# audio_interface_board.net
KiCad netlist of a schematic drawn in EasyEDA Pro
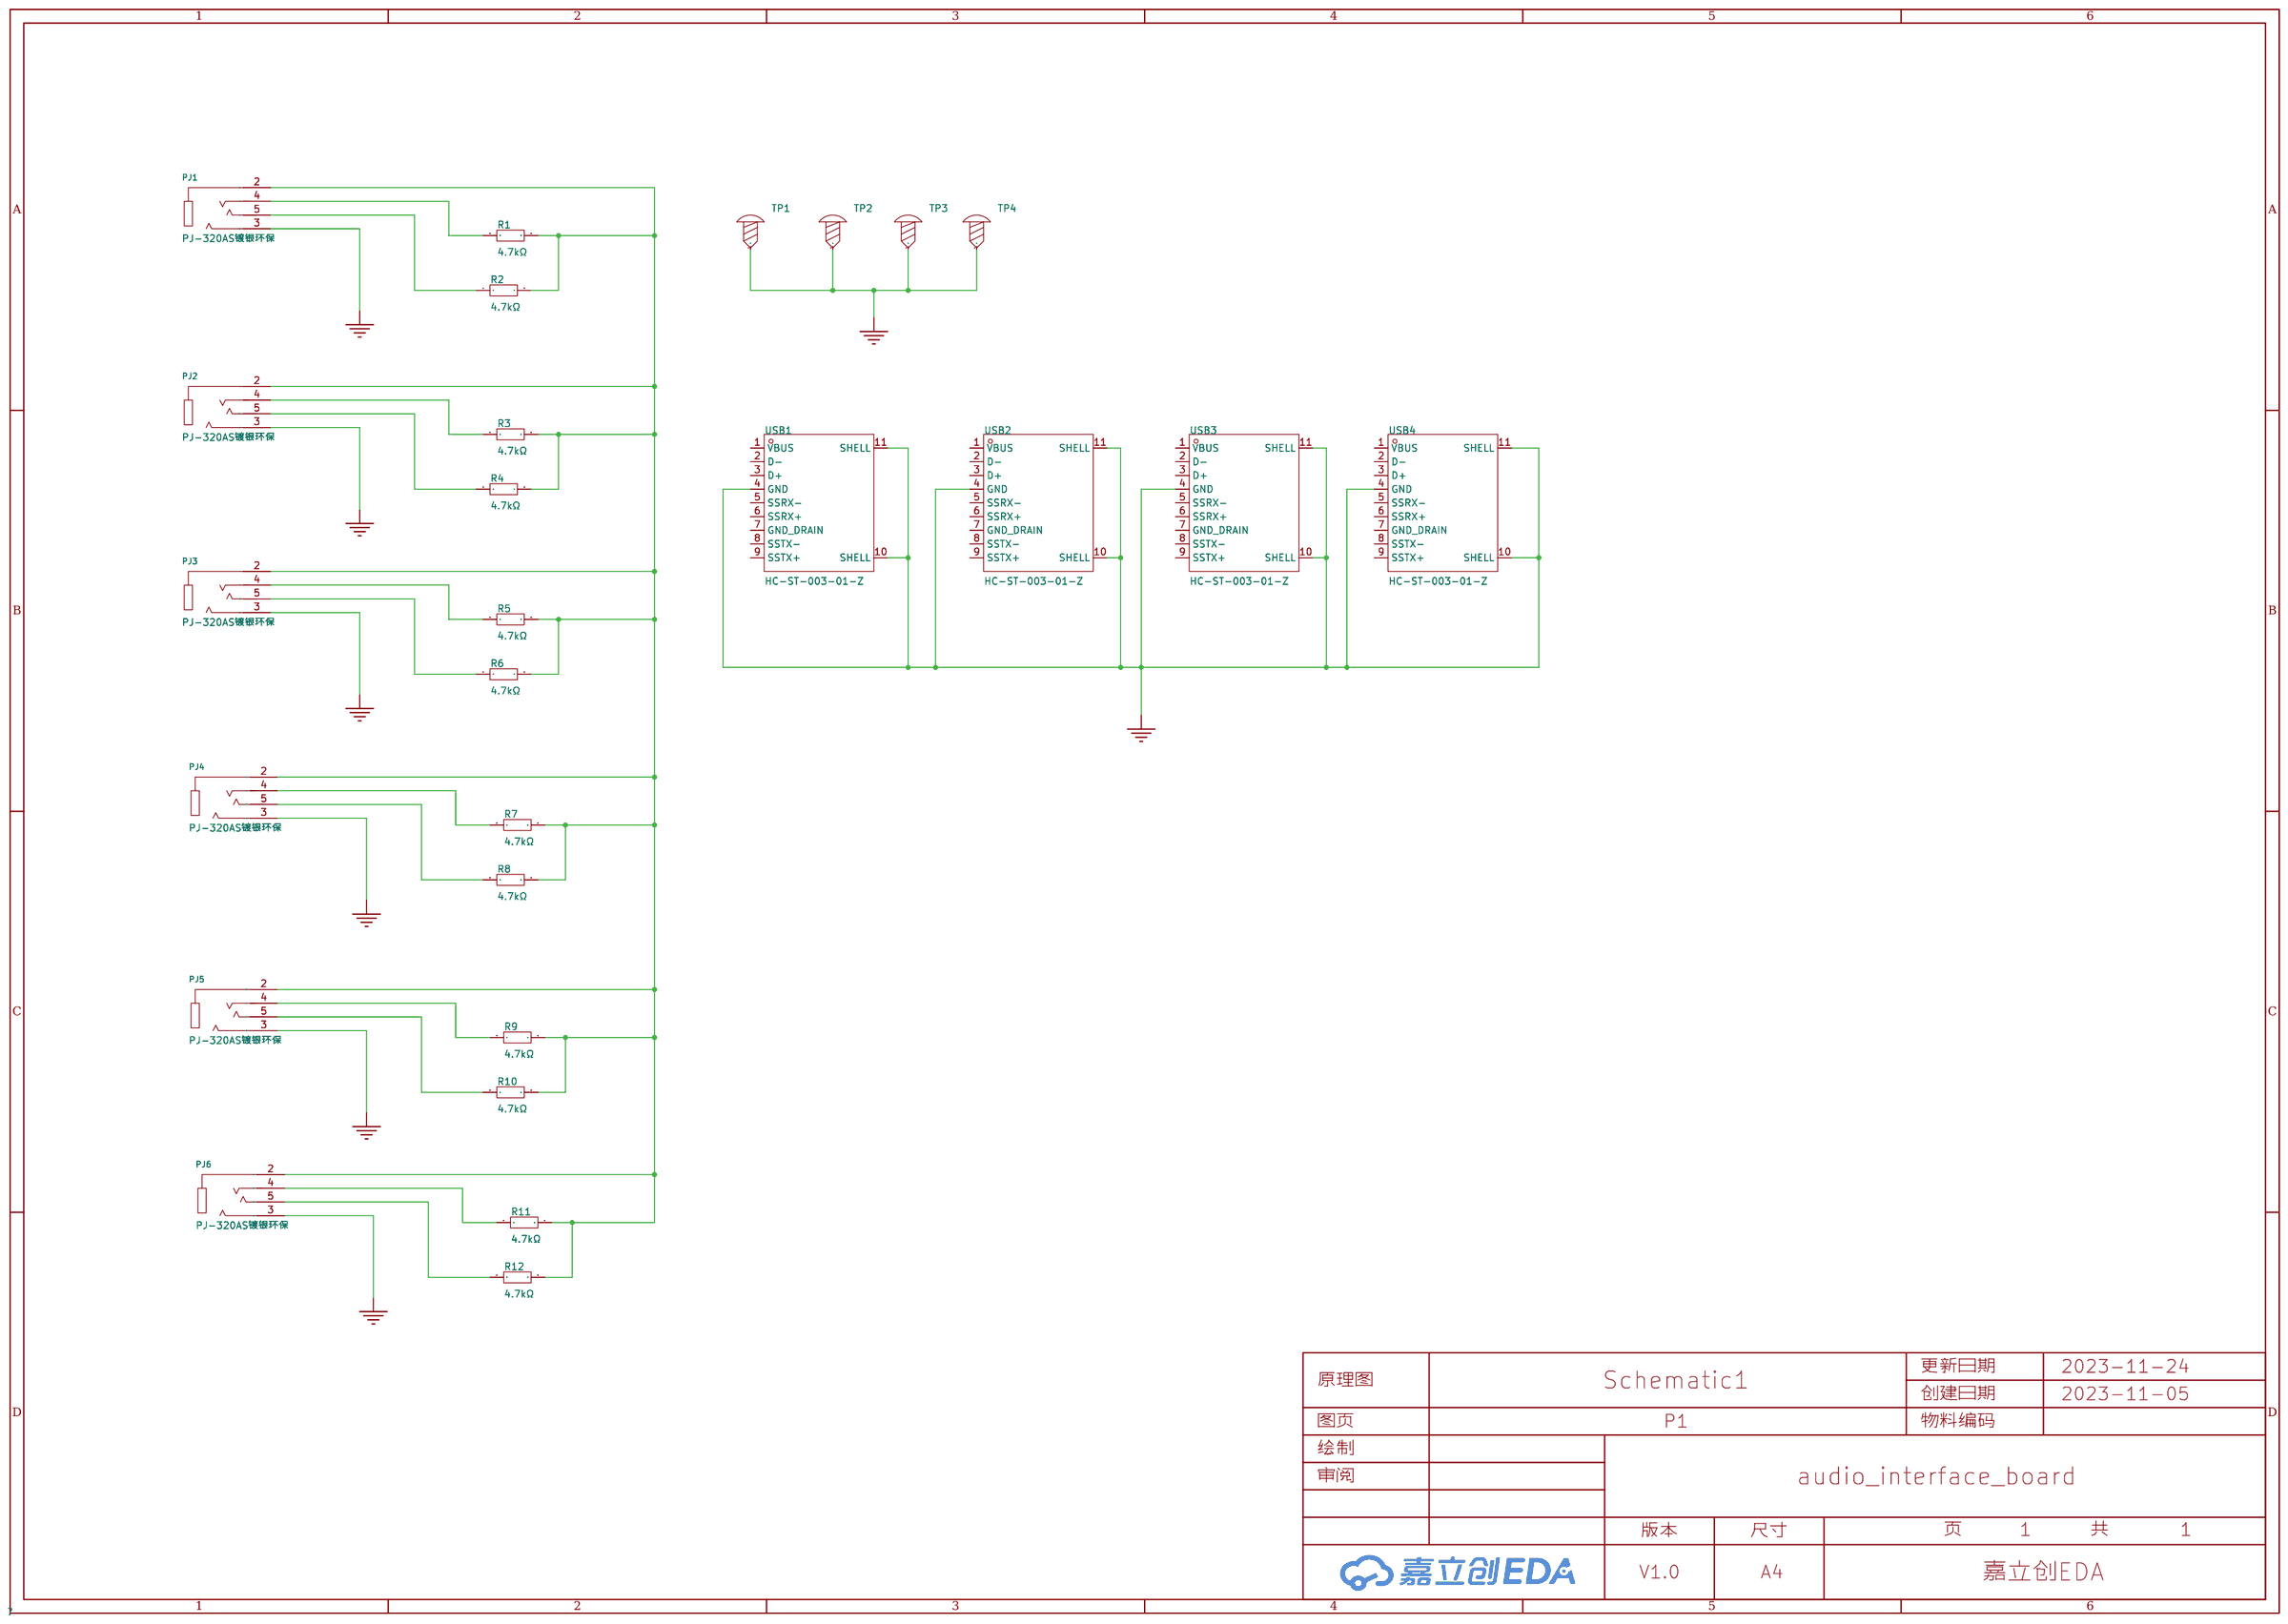
[diagram p0: schematic sheet]

(export (version "E")
  (design (tool "Eeschema 10.0.6"))
  (components
    (comp (ref "PJ1")
      (value "PJ-320AS镀银环保")
      (footprint "easyedapro:AUDIO-TH_HAOYU_PJ-320AS")
      (description "3.5mm耳机插座")
      (fields (field (name "Manufacturer") "HOOYA(皓宇电子)"))
      (libsource (lib "easyedapro") (part "PJ-320AS"))
    )
    (comp (ref "PJ2")
      (value "PJ-320AS镀银环保")
      (footprint "easyedapro:AUDIO-TH_HAOYU_PJ-320AS")
      (description "3.5mm耳机插座")
      (fields (field (name "Manufacturer") "HOOYA(皓宇电子)"))
      (libsource (lib "easyedapro") (part "PJ-320AS"))
    )
    (comp (ref "PJ3")
      (value "PJ-320AS镀银环保")
      (footprint "easyedapro:AUDIO-TH_HAOYU_PJ-320AS")
      (description "3.5mm耳机插座")
      (fields (field (name "Manufacturer") "HOOYA(皓宇电子)"))
      (libsource (lib "easyedapro") (part "PJ-320AS"))
    )
    (comp (ref "PJ4")
      (value "PJ-320AS镀银环保")
      (footprint "easyedapro:AUDIO-TH_HAOYU_PJ-320AS")
      (description "3.5mm耳机插座")
      (fields (field (name "Manufacturer") "HOOYA(皓宇电子)"))
      (libsource (lib "easyedapro") (part "PJ-320AS"))
    )
    (comp (ref "PJ5")
      (value "PJ-320AS镀银环保")
      (footprint "easyedapro:AUDIO-TH_HAOYU_PJ-320AS")
      (description "3.5mm耳机插座")
      (fields (field (name "Manufacturer") "HOOYA(皓宇电子)"))
      (libsource (lib "easyedapro") (part "PJ-320AS"))
    )
    (comp (ref "PJ6")
      (value "PJ-320AS镀银环保")
      (footprint "easyedapro:AUDIO-TH_HAOYU_PJ-320AS")
      (description "3.5mm耳机插座")
      (fields (field (name "Manufacturer") "HOOYA(皓宇电子)"))
      (libsource (lib "easyedapro") (part "PJ-320AS"))
    )
    (comp (ref "R1")
      (value "4.7kΩ")
      (footprint "easyedapro:R0805")
      (libsource (lib "easyedapro") (part "电阻"))
    )
    (comp (ref "R2")
      (value "4.7kΩ")
      (footprint "easyedapro:R0805")
      (libsource (lib "easyedapro") (part "电阻"))
    )
    (comp (ref "R3")
      (value "4.7kΩ")
      (footprint "easyedapro:R0805")
      (libsource (lib "easyedapro") (part "电阻"))
    )
    (comp (ref "R4")
      (value "4.7kΩ")
      (footprint "easyedapro:R0805")
      (libsource (lib "easyedapro") (part "电阻"))
    )
    (comp (ref "R5")
      (value "4.7kΩ")
      (footprint "easyedapro:R0805")
      (libsource (lib "easyedapro") (part "电阻"))
    )
    (comp (ref "R6")
      (value "4.7kΩ")
      (footprint "easyedapro:R0805")
      (libsource (lib "easyedapro") (part "电阻"))
    )
    (comp (ref "R7")
      (value "4.7kΩ")
      (footprint "easyedapro:R0805")
      (libsource (lib "easyedapro") (part "电阻"))
    )
    (comp (ref "R8")
      (value "4.7kΩ")
      (footprint "easyedapro:R0805")
      (libsource (lib "easyedapro") (part "电阻"))
    )
    (comp (ref "R9")
      (value "4.7kΩ")
      (footprint "easyedapro:R0805")
      (libsource (lib "easyedapro") (part "电阻"))
    )
    (comp (ref "R10")
      (value "4.7kΩ")
      (footprint "easyedapro:R0805")
      (libsource (lib "easyedapro") (part "电阻"))
    )
    (comp (ref "R11")
      (value "4.7kΩ")
      (footprint "easyedapro:R0805")
      (libsource (lib "easyedapro") (part "电阻"))
    )
    (comp (ref "R12")
      (value "4.7kΩ")
      (footprint "easyedapro:R0805")
      (libsource (lib "easyedapro") (part "电阻"))
    )
    (comp (ref "TP1") (value "~") (footprint "easyedapro:M3螺丝") (libsource (lib "easyedapro") (part "螺丝孔")))
    (comp (ref "TP2") (value "~") (footprint "easyedapro:M3螺丝") (libsource (lib "easyedapro") (part "螺丝孔")))
    (comp (ref "TP3") (value "~") (footprint "easyedapro:M3螺丝") (libsource (lib "easyedapro") (part "螺丝孔")))
    (comp (ref "TP4") (value "~") (footprint "easyedapro:M3螺丝") (libsource (lib "easyedapro") (part "螺丝孔")))
    (comp (ref "USB1")
      (value "HC-ST-003-01-Z")
      (footprint "easyedapro:USB-3.0-A-TH_HC-ST-003-01-Z")
      (description "连接器类型:Type-A;标准:USB 3.0;公母:母座;触点数量:9;端口数量:1;安装方式:弯插;额定电流 - 电源:1.5A;工作温度范围:-25°C~+70°C;")
      (fields (field (name "Manufacturer") "HCTL(华灿天禄)"))
      (libsource (lib "easyedapro") (part "HC-ST-003-01-Z"))
    )
    (comp (ref "USB2")
      (value "HC-ST-003-01-Z")
      (footprint "easyedapro:USB-3.0-A-TH_HC-ST-003-01-Z")
      (description "连接器类型:Type-A;标准:USB 3.0;公母:母座;触点数量:9;端口数量:1;安装方式:弯插;额定电流 - 电源:1.5A;工作温度范围:-25°C~+70°C;")
      (fields (field (name "Manufacturer") "HCTL(华灿天禄)"))
      (libsource (lib "easyedapro") (part "HC-ST-003-01-Z"))
    )
    (comp (ref "USB3")
      (value "HC-ST-003-01-Z")
      (footprint "easyedapro:USB-3.0-A-TH_HC-ST-003-01-Z")
      (description "连接器类型:Type-A;标准:USB 3.0;公母:母座;触点数量:9;端口数量:1;安装方式:弯插;额定电流 - 电源:1.5A;工作温度范围:-25°C~+70°C;")
      (fields (field (name "Manufacturer") "HCTL(华灿天禄)"))
      (libsource (lib "easyedapro") (part "HC-ST-003-01-Z"))
    )
    (comp (ref "USB4")
      (value "HC-ST-003-01-Z")
      (footprint "easyedapro:USB-3.0-A-TH_HC-ST-003-01-Z")
      (description "连接器类型:Type-A;标准:USB 3.0;公母:母座;触点数量:9;端口数量:1;安装方式:弯插;额定电流 - 电源:1.5A;工作温度范围:-25°C~+70°C;")
      (fields (field (name "Manufacturer") "HCTL(华灿天禄)"))
      (libsource (lib "easyedapro") (part "HC-ST-003-01-Z"))
    )
  )
  (nets
    (net (code "1") (name "GND") (class "Default")
      (node (ref "PJ1") (pin "3") (pinfunction "3_3") (pintype "input"))
      (node (ref "PJ2") (pin "3") (pinfunction "3_3") (pintype "input"))
      (node (ref "PJ3") (pin "3") (pinfunction "3_3") (pintype "input"))
      (node (ref "PJ4") (pin "3") (pinfunction "3_3") (pintype "input"))
      (node (ref "PJ5") (pin "3") (pinfunction "3_3") (pintype "input"))
      (node (ref "PJ6") (pin "3") (pinfunction "3_3") (pintype "input"))
      (node (ref "TP1") (pin "1") (pinfunction "1_1") (pintype "input"))
      (node (ref "TP2") (pin "1") (pinfunction "1_1") (pintype "input"))
      (node (ref "TP3") (pin "1") (pinfunction "1_1") (pintype "input"))
      (node (ref "TP4") (pin "1") (pinfunction "1_1") (pintype "input"))
      (node (ref "USB1") (pin "10") (pinfunction "SHELL_10") (pintype "unspecified"))
      (node (ref "USB1") (pin "11") (pinfunction "SHELL_11") (pintype "unspecified"))
      (node (ref "USB1") (pin "4") (pinfunction "GND_4") (pintype "unspecified"))
      (node (ref "USB2") (pin "10") (pinfunction "SHELL_10") (pintype "unspecified"))
      (node (ref "USB2") (pin "11") (pinfunction "SHELL_11") (pintype "unspecified"))
      (node (ref "USB2") (pin "4") (pinfunction "GND_4") (pintype "unspecified"))
      (node (ref "USB3") (pin "10") (pinfunction "SHELL_10") (pintype "unspecified"))
      (node (ref "USB3") (pin "11") (pinfunction "SHELL_11") (pintype "unspecified"))
      (node (ref "USB3") (pin "4") (pinfunction "GND_4") (pintype "unspecified"))
      (node (ref "USB4") (pin "10") (pinfunction "SHELL_10") (pintype "unspecified"))
      (node (ref "USB4") (pin "11") (pinfunction "SHELL_11") (pintype "unspecified"))
      (node (ref "USB4") (pin "4") (pinfunction "GND_4") (pintype "unspecified"))
    )
    (net (code "2") (name "Net-(PJ1-Pad2)") (class "Default")
      (node (ref "PJ1") (pin "2") (pinfunction "2_2") (pintype "input"))
      (node (ref "PJ2") (pin "2") (pinfunction "2_2") (pintype "input"))
      (node (ref "PJ3") (pin "2") (pinfunction "2_2") (pintype "input"))
      (node (ref "PJ4") (pin "2") (pinfunction "2_2") (pintype "input"))
      (node (ref "PJ5") (pin "2") (pinfunction "2_2") (pintype "input"))
      (node (ref "PJ6") (pin "2") (pinfunction "2_2") (pintype "input"))
      (node (ref "R1") (pin "2") (pinfunction "2_2") (pintype "input"))
      (node (ref "R10") (pin "2") (pinfunction "2_2") (pintype "input"))
      (node (ref "R11") (pin "2") (pinfunction "2_2") (pintype "input"))
      (node (ref "R12") (pin "2") (pinfunction "2_2") (pintype "input"))
      (node (ref "R2") (pin "2") (pinfunction "2_2") (pintype "input"))
      (node (ref "R3") (pin "2") (pinfunction "2_2") (pintype "input"))
      (node (ref "R4") (pin "2") (pinfunction "2_2") (pintype "input"))
      (node (ref "R5") (pin "2") (pinfunction "2_2") (pintype "input"))
      (node (ref "R6") (pin "2") (pinfunction "2_2") (pintype "input"))
      (node (ref "R7") (pin "2") (pinfunction "2_2") (pintype "input"))
      (node (ref "R8") (pin "2") (pinfunction "2_2") (pintype "input"))
      (node (ref "R9") (pin "2") (pinfunction "2_2") (pintype "input"))
    )
    (net (code "3") (name "Net-(PJ1-Pad4)") (class "Default")
      (node (ref "PJ1") (pin "4") (pinfunction "4_4") (pintype "input"))
      (node (ref "R1") (pin "1") (pinfunction "1_1") (pintype "input"))
    )
    (net (code "4") (name "Net-(PJ1-Pad5)") (class "Default")
      (node (ref "PJ1") (pin "5") (pinfunction "5_5") (pintype "input"))
      (node (ref "R2") (pin "1") (pinfunction "1_1") (pintype "input"))
    )
    (net (code "5") (name "Net-(PJ2-Pad4)") (class "Default")
      (node (ref "PJ2") (pin "4") (pinfunction "4_4") (pintype "input"))
      (node (ref "R3") (pin "1") (pinfunction "1_1") (pintype "input"))
    )
    (net (code "6") (name "Net-(PJ2-Pad5)") (class "Default")
      (node (ref "PJ2") (pin "5") (pinfunction "5_5") (pintype "input"))
      (node (ref "R4") (pin "1") (pinfunction "1_1") (pintype "input"))
    )
    (net (code "7") (name "Net-(PJ3-Pad4)") (class "Default")
      (node (ref "PJ3") (pin "4") (pinfunction "4_4") (pintype "input"))
      (node (ref "R5") (pin "1") (pinfunction "1_1") (pintype "input"))
    )
    (net (code "8") (name "Net-(PJ3-Pad5)") (class "Default")
      (node (ref "PJ3") (pin "5") (pinfunction "5_5") (pintype "input"))
      (node (ref "R6") (pin "1") (pinfunction "1_1") (pintype "input"))
    )
    (net (code "9") (name "Net-(PJ4-Pad4)") (class "Default")
      (node (ref "PJ4") (pin "4") (pinfunction "4_4") (pintype "input"))
      (node (ref "R7") (pin "1") (pinfunction "1_1") (pintype "input"))
    )
    (net (code "10") (name "Net-(PJ4-Pad5)") (class "Default")
      (node (ref "PJ4") (pin "5") (pinfunction "5_5") (pintype "input"))
      (node (ref "R8") (pin "1") (pinfunction "1_1") (pintype "input"))
    )
    (net (code "11") (name "Net-(PJ5-Pad4)") (class "Default")
      (node (ref "PJ5") (pin "4") (pinfunction "4_4") (pintype "input"))
      (node (ref "R9") (pin "1") (pinfunction "1_1") (pintype "input"))
    )
    (net (code "12") (name "Net-(PJ5-Pad5)") (class "Default")
      (node (ref "PJ5") (pin "5") (pinfunction "5_5") (pintype "input"))
      (node (ref "R10") (pin "1") (pinfunction "1_1") (pintype "input"))
    )
    (net (code "13") (name "Net-(PJ6-Pad4)") (class "Default")
      (node (ref "PJ6") (pin "4") (pinfunction "4_4") (pintype "input"))
      (node (ref "R11") (pin "1") (pinfunction "1_1") (pintype "input"))
    )
    (net (code "14") (name "Net-(PJ6-Pad5)") (class "Default")
      (node (ref "PJ6") (pin "5") (pinfunction "5_5") (pintype "input"))
      (node (ref "R12") (pin "1") (pinfunction "1_1") (pintype "input"))
    )
    (net (code "15") (name "unconnected-(USB1-D+-Pad3)") (class "Default")
      (node (ref "USB1") (pin "3") (pinfunction "D+_3") (pintype "unspecified"))
    )
    (net (code "16") (name "unconnected-(USB1-D--Pad2)") (class "Default")
      (node (ref "USB1") (pin "2") (pinfunction "D-_2") (pintype "unspecified"))
    )
    (net (code "17") (name "unconnected-(USB1-GND_DRAIN-Pad7)") (class "Default")
      (node (ref "USB1") (pin "7") (pinfunction "GND_DRAIN_7") (pintype "unspecified"))
    )
    (net (code "18") (name "unconnected-(USB1-SSRX+-Pad6)") (class "Default")
      (node (ref "USB1") (pin "6") (pinfunction "SSRX+_6") (pintype "unspecified"))
    )
    (net (code "19") (name "unconnected-(USB1-SSRX--Pad5)") (class "Default")
      (node (ref "USB1") (pin "5") (pinfunction "SSRX-_5") (pintype "unspecified"))
    )
    (net (code "20") (name "unconnected-(USB1-SSTX+-Pad9)") (class "Default")
      (node (ref "USB1") (pin "9") (pinfunction "SSTX+_9") (pintype "unspecified"))
    )
    (net (code "21") (name "unconnected-(USB1-SSTX--Pad8)") (class "Default")
      (node (ref "USB1") (pin "8") (pinfunction "SSTX-_8") (pintype "unspecified"))
    )
    (net (code "22") (name "unconnected-(USB1-VBUS-Pad1)") (class "Default")
      (node (ref "USB1") (pin "1") (pinfunction "VBUS_1") (pintype "unspecified"))
    )
    (net (code "23") (name "unconnected-(USB2-D+-Pad3)") (class "Default")
      (node (ref "USB2") (pin "3") (pinfunction "D+_3") (pintype "unspecified"))
    )
    (net (code "24") (name "unconnected-(USB2-D--Pad2)") (class "Default")
      (node (ref "USB2") (pin "2") (pinfunction "D-_2") (pintype "unspecified"))
    )
    (net (code "25") (name "unconnected-(USB2-GND_DRAIN-Pad7)") (class "Default")
      (node (ref "USB2") (pin "7") (pinfunction "GND_DRAIN_7") (pintype "unspecified"))
    )
    (net (code "26") (name "unconnected-(USB2-SSRX+-Pad6)") (class "Default")
      (node (ref "USB2") (pin "6") (pinfunction "SSRX+_6") (pintype "unspecified"))
    )
    (net (code "27") (name "unconnected-(USB2-SSRX--Pad5)") (class "Default")
      (node (ref "USB2") (pin "5") (pinfunction "SSRX-_5") (pintype "unspecified"))
    )
    (net (code "28") (name "unconnected-(USB2-SSTX+-Pad9)") (class "Default")
      (node (ref "USB2") (pin "9") (pinfunction "SSTX+_9") (pintype "unspecified"))
    )
    (net (code "29") (name "unconnected-(USB2-SSTX--Pad8)") (class "Default")
      (node (ref "USB2") (pin "8") (pinfunction "SSTX-_8") (pintype "unspecified"))
    )
    (net (code "30") (name "unconnected-(USB2-VBUS-Pad1)") (class "Default")
      (node (ref "USB2") (pin "1") (pinfunction "VBUS_1") (pintype "unspecified"))
    )
    (net (code "31") (name "unconnected-(USB3-D+-Pad3)") (class "Default")
      (node (ref "USB3") (pin "3") (pinfunction "D+_3") (pintype "unspecified"))
    )
    (net (code "32") (name "unconnected-(USB3-D--Pad2)") (class "Default")
      (node (ref "USB3") (pin "2") (pinfunction "D-_2") (pintype "unspecified"))
    )
    (net (code "33") (name "unconnected-(USB3-GND_DRAIN-Pad7)") (class "Default")
      (node (ref "USB3") (pin "7") (pinfunction "GND_DRAIN_7") (pintype "unspecified"))
    )
    (net (code "34") (name "unconnected-(USB3-SSRX+-Pad6)") (class "Default")
      (node (ref "USB3") (pin "6") (pinfunction "SSRX+_6") (pintype "unspecified"))
    )
    (net (code "35") (name "unconnected-(USB3-SSRX--Pad5)") (class "Default")
      (node (ref "USB3") (pin "5") (pinfunction "SSRX-_5") (pintype "unspecified"))
    )
    (net (code "36") (name "unconnected-(USB3-SSTX+-Pad9)") (class "Default")
      (node (ref "USB3") (pin "9") (pinfunction "SSTX+_9") (pintype "unspecified"))
    )
    (net (code "37") (name "unconnected-(USB3-SSTX--Pad8)") (class "Default")
      (node (ref "USB3") (pin "8") (pinfunction "SSTX-_8") (pintype "unspecified"))
    )
    (net (code "38") (name "unconnected-(USB3-VBUS-Pad1)") (class "Default")
      (node (ref "USB3") (pin "1") (pinfunction "VBUS_1") (pintype "unspecified"))
    )
    (net (code "39") (name "unconnected-(USB4-D+-Pad3)") (class "Default")
      (node (ref "USB4") (pin "3") (pinfunction "D+_3") (pintype "unspecified"))
    )
    (net (code "40") (name "unconnected-(USB4-D--Pad2)") (class "Default")
      (node (ref "USB4") (pin "2") (pinfunction "D-_2") (pintype "unspecified"))
    )
    (net (code "41") (name "unconnected-(USB4-GND_DRAIN-Pad7)") (class "Default")
      (node (ref "USB4") (pin "7") (pinfunction "GND_DRAIN_7") (pintype "unspecified"))
    )
    (net (code "42") (name "unconnected-(USB4-SSRX+-Pad6)") (class "Default")
      (node (ref "USB4") (pin "6") (pinfunction "SSRX+_6") (pintype "unspecified"))
    )
    (net (code "43") (name "unconnected-(USB4-SSRX--Pad5)") (class "Default")
      (node (ref "USB4") (pin "5") (pinfunction "SSRX-_5") (pintype "unspecified"))
    )
    (net (code "44") (name "unconnected-(USB4-SSTX+-Pad9)") (class "Default")
      (node (ref "USB4") (pin "9") (pinfunction "SSTX+_9") (pintype "unspecified"))
    )
    (net (code "45") (name "unconnected-(USB4-SSTX--Pad8)") (class "Default")
      (node (ref "USB4") (pin "8") (pinfunction "SSTX-_8") (pintype "unspecified"))
    )
    (net (code "46") (name "unconnected-(USB4-VBUS-Pad1)") (class "Default")
      (node (ref "USB4") (pin "1") (pinfunction "VBUS_1") (pintype "unspecified"))
    )
  )
)
